# FTS_V1_0.net
KiCad netlist of a schematic drawn in EAGLE
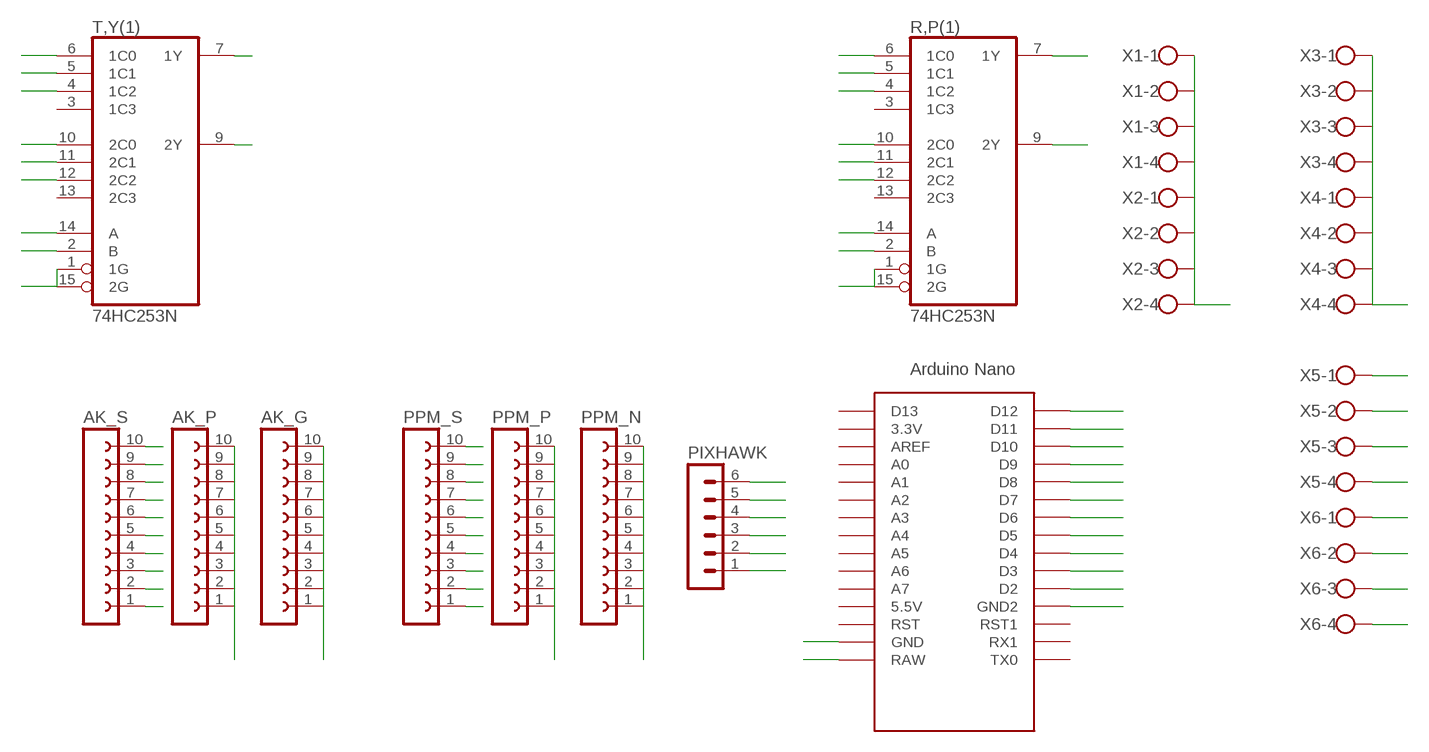
[diagram p0: schematic, sheet 1]

(export (version "E")
  (design (tool "Eeschema 10.0.6"))
  (components
    (comp (ref "AK_G")
      (value "FE10-1")
      (footprint "eagle-import:FE10")
      (libsource (lib "eagle-import") (part "FE10-1"))
    )
    (comp (ref "AK_P")
      (value "FE10-1")
      (footprint "eagle-import:FE10")
      (libsource (lib "eagle-import") (part "FE10-1"))
    )
    (comp (ref "AK_S")
      (value "FE10-1")
      (footprint "eagle-import:FE10")
      (libsource (lib "eagle-import") (part "FE10-1"))
    )
    (comp (ref "PIXHAWK")
      (value "MA06-1")
      (footprint "eagle-import:MA06-1")
      (libsource (lib "eagle-import") (part "MA06-1"))
    )
    (comp (ref "PPM_N")
      (value "FE10-1")
      (footprint "eagle-import:FE10")
      (libsource (lib "eagle-import") (part "FE10-1"))
    )
    (comp (ref "PPM_P")
      (value "FE10-1")
      (footprint "eagle-import:FE10")
      (libsource (lib "eagle-import") (part "FE10-1"))
    )
    (comp (ref "PPM_S")
      (value "FE10-1")
      (footprint "eagle-import:FE10")
      (libsource (lib "eagle-import") (part "FE10-1"))
    )
    (comp (ref "R,P(1)")
      (value "74HC253N")
      (footprint "eagle-import:DIL16")
      (libsource (lib "eagle-import") (part "74253NHC"))
    )
    (comp (ref "T,Y(1)")
      (value "74HC253N")
      (footprint "eagle-import:DIL16")
      (libsource (lib "eagle-import") (part "74253NHC"))
    )
    (comp (ref "U$1")
      (value "NANO")
      (footprint "eagle-import:NANO")
      (libsource (lib "eagle-import") (part "NANO"))
    )
    (comp (ref "X1")
      (value "W237-4")
      (footprint "eagle-import:W237-4")
      (libsource (lib "eagle-import") (part "W237-4"))
    )
    (comp (ref "X2")
      (value "W237-4")
      (footprint "eagle-import:W237-4")
      (libsource (lib "eagle-import") (part "W237-4"))
    )
    (comp (ref "X3")
      (value "W237-4")
      (footprint "eagle-import:W237-4")
      (libsource (lib "eagle-import") (part "W237-4"))
    )
    (comp (ref "X4")
      (value "W237-4")
      (footprint "eagle-import:W237-4")
      (libsource (lib "eagle-import") (part "W237-4"))
    )
    (comp (ref "X5")
      (value "W237-4")
      (footprint "eagle-import:W237-4")
      (libsource (lib "eagle-import") (part "W237-4"))
    )
    (comp (ref "X6")
      (value "W237-4")
      (footprint "eagle-import:W237-4")
      (libsource (lib "eagle-import") (part "W237-4"))
    )
  )
  (nets
    (net (code "1") (name "/AUX2") (class "Default")
      (node (ref "AK_S") (pin "7") (pinfunction "7_7") (pintype "passive"))
      (node (ref "U$1") (pin "D6") (pinfunction "D6_D6") (pintype "bidirectional"))
    )
    (net (code "2") (name "/DROP") (class "Default")
      (node (ref "AK_S") (pin "10") (pinfunction "10_10") (pintype "passive"))
      (node (ref "X6") (pin "4") (pinfunction "KL_4") (pintype "passive"))
    )
    (net (code "3") (name "/GBL-P") (class "Default")
      (node (ref "AK_S") (pin "9") (pinfunction "9_9") (pintype "passive"))
      (node (ref "X6") (pin "3") (pinfunction "KL_3") (pintype "passive"))
    )
    (net (code "4") (name "/GBL-R") (class "Default")
      (node (ref "AK_S") (pin "8") (pinfunction "8_8") (pintype "passive"))
      (node (ref "X6") (pin "2") (pinfunction "KL_2") (pintype "passive"))
    )
    (net (code "5") (name "/GEAR") (class "Default")
      (node (ref "AK_S") (pin "6") (pinfunction "6_6") (pintype "passive"))
      (node (ref "U$1") (pin "D5") (pinfunction "D5_D5") (pintype "bidirectional"))
    )
    (net (code "6") (name "/GND") (class "Default")
      (node (ref "AK_G") (pin "1") (pinfunction "1_1") (pintype "passive"))
      (node (ref "AK_G") (pin "10") (pinfunction "10_10") (pintype "passive"))
      (node (ref "AK_G") (pin "2") (pinfunction "2_2") (pintype "passive"))
      (node (ref "AK_G") (pin "3") (pinfunction "3_3") (pintype "passive"))
      (node (ref "AK_G") (pin "4") (pinfunction "4_4") (pintype "passive"))
      (node (ref "AK_G") (pin "5") (pinfunction "5_5") (pintype "passive"))
      (node (ref "AK_G") (pin "6") (pinfunction "6_6") (pintype "passive"))
      (node (ref "AK_G") (pin "7") (pinfunction "7_7") (pintype "passive"))
      (node (ref "AK_G") (pin "8") (pinfunction "8_8") (pintype "passive"))
      (node (ref "AK_G") (pin "9") (pinfunction "9_9") (pintype "passive"))
      (node (ref "PIXHAWK") (pin "6") (pinfunction "6_6") (pintype "passive"))
      (node (ref "PPM_N") (pin "1") (pinfunction "1_1") (pintype "passive"))
      (node (ref "PPM_N") (pin "10") (pinfunction "10_10") (pintype "passive"))
      (node (ref "PPM_N") (pin "2") (pinfunction "2_2") (pintype "passive"))
      (node (ref "PPM_N") (pin "3") (pinfunction "3_3") (pintype "passive"))
      (node (ref "PPM_N") (pin "4") (pinfunction "4_4") (pintype "passive"))
      (node (ref "PPM_N") (pin "5") (pinfunction "5_5") (pintype "passive"))
      (node (ref "PPM_N") (pin "6") (pinfunction "6_6") (pintype "passive"))
      (node (ref "PPM_N") (pin "7") (pinfunction "7_7") (pintype "passive"))
      (node (ref "PPM_N") (pin "8") (pinfunction "8_8") (pintype "passive"))
      (node (ref "PPM_N") (pin "9") (pinfunction "9_9") (pintype "passive"))
      (node (ref "R,P(1)") (pin "1") (pinfunction "1G_1") (pintype "input"))
      (node (ref "R,P(1)") (pin "15") (pinfunction "2G_15") (pintype "input"))
      (node (ref "T,Y(1)") (pin "1") (pinfunction "1G_1") (pintype "input"))
      (node (ref "T,Y(1)") (pin "15") (pinfunction "2G_15") (pintype "input"))
      (node (ref "U$1") (pin "GND") (pinfunction "GND_GND") (pintype "bidirectional"))
      (node (ref "U$1") (pin "GND1") (pinfunction "GND2_GND1") (pintype "bidirectional"))
      (node (ref "X3") (pin "1") (pinfunction "KL_1") (pintype "passive"))
      (node (ref "X3") (pin "2") (pinfunction "KL_2") (pintype "passive"))
      (node (ref "X3") (pin "3") (pinfunction "KL_3") (pintype "passive"))
      (node (ref "X3") (pin "4") (pinfunction "KL_4") (pintype "passive"))
      (node (ref "X4") (pin "1") (pinfunction "KL_1") (pintype "passive"))
      (node (ref "X4") (pin "2") (pinfunction "KL_2") (pintype "passive"))
      (node (ref "X4") (pin "3") (pinfunction "KL_3") (pintype "passive"))
      (node (ref "X4") (pin "4") (pinfunction "KL_4") (pintype "passive"))
    )
    (net (code "7") (name "/PX-P") (class "Default")
      (node (ref "PIXHAWK") (pin "2") (pinfunction "2_2") (pintype "passive"))
      (node (ref "R,P(1)") (pin "11") (pinfunction "2C1_11") (pintype "input"))
    )
    (net (code "8") (name "/PX-R") (class "Default")
      (node (ref "PIXHAWK") (pin "1") (pinfunction "1_1") (pintype "passive"))
      (node (ref "R,P(1)") (pin "5") (pinfunction "1C1_5") (pintype "input"))
    )
    (net (code "9") (name "/PX-T") (class "Default")
      (node (ref "PIXHAWK") (pin "3") (pinfunction "3_3") (pintype "passive"))
      (node (ref "T,Y(1)") (pin "5") (pinfunction "1C1_5") (pintype "input"))
    )
    (net (code "10") (name "/PX-Y") (class "Default")
      (node (ref "PIXHAWK") (pin "4") (pinfunction "4_4") (pintype "passive"))
      (node (ref "T,Y(1)") (pin "11") (pinfunction "2C1_11") (pintype "input"))
    )
    (net (code "11") (name "/RX-FM") (class "Default")
      (node (ref "AK_S") (pin "5") (pinfunction "5_5") (pintype "passive"))
      (node (ref "PPM_S") (pin "5") (pinfunction "5_5") (pintype "passive"))
    )
    (net (code "12") (name "/RX-P") (class "Default")
      (node (ref "AK_S") (pin "2") (pinfunction "2_2") (pintype "passive"))
      (node (ref "PPM_S") (pin "2") (pinfunction "2_2") (pintype "passive"))
      (node (ref "R,P(1)") (pin "10") (pinfunction "2C0_10") (pintype "input"))
    )
    (net (code "13") (name "/RX-R") (class "Default")
      (node (ref "AK_S") (pin "1") (pinfunction "1_1") (pintype "passive"))
      (node (ref "PPM_S") (pin "1") (pinfunction "1_1") (pintype "passive"))
      (node (ref "R,P(1)") (pin "6") (pinfunction "1C0_6") (pintype "input"))
    )
    (net (code "14") (name "/RX-T") (class "Default")
      (node (ref "AK_S") (pin "3") (pinfunction "3_3") (pintype "passive"))
      (node (ref "PPM_S") (pin "3") (pinfunction "3_3") (pintype "passive"))
      (node (ref "T,Y(1)") (pin "6") (pinfunction "1C0_6") (pintype "input"))
      (node (ref "U$1") (pin "D12") (pinfunction "D12_D12") (pintype "bidirectional"))
    )
    (net (code "15") (name "/RX-Y") (class "Default")
      (node (ref "AK_S") (pin "4") (pinfunction "4_4") (pintype "passive"))
      (node (ref "PPM_S") (pin "4") (pinfunction "4_4") (pintype "passive"))
      (node (ref "T,Y(1)") (pin "10") (pinfunction "2C0_10") (pintype "input"))
    )
    (net (code "16") (name "/S-P") (class "Default")
      (node (ref "R,P(1)") (pin "9") (pinfunction "2Y_9") (pintype "tri_state"))
      (node (ref "X5") (pin "2") (pinfunction "KL_2") (pintype "passive"))
    )
    (net (code "17") (name "/S-R") (class "Default")
      (node (ref "R,P(1)") (pin "7") (pinfunction "1Y_7") (pintype "tri_state"))
      (node (ref "X5") (pin "1") (pinfunction "KL_1") (pintype "passive"))
    )
    (net (code "18") (name "/S-T") (class "Default")
      (node (ref "T,Y(1)") (pin "7") (pinfunction "1Y_7") (pintype "tri_state"))
      (node (ref "X5") (pin "3") (pinfunction "KL_3") (pintype "passive"))
    )
    (net (code "19") (name "/S-Y") (class "Default")
      (node (ref "T,Y(1)") (pin "9") (pinfunction "2Y_9") (pintype "tri_state"))
      (node (ref "X5") (pin "4") (pinfunction "KL_4") (pintype "passive"))
      (node (ref "X6") (pin "1") (pinfunction "KL_1") (pintype "passive"))
    )
    (net (code "20") (name "/S1") (class "Default")
      (node (ref "R,P(1)") (pin "14") (pinfunction "A_14") (pintype "input"))
      (node (ref "T,Y(1)") (pin "14") (pinfunction "A_14") (pintype "input"))
      (node (ref "U$1") (pin "D2") (pinfunction "D2_D2") (pintype "bidirectional"))
    )
    (net (code "21") (name "/S2") (class "Default")
      (node (ref "R,P(1)") (pin "2") (pinfunction "B_2") (pintype "input"))
      (node (ref "T,Y(1)") (pin "2") (pinfunction "B_2") (pintype "input"))
      (node (ref "U$1") (pin "D3") (pinfunction "D3_D3") (pintype "bidirectional"))
    )
    (net (code "22") (name "/VCC") (class "Default")
      (node (ref "AK_P") (pin "1") (pinfunction "1_1") (pintype "passive"))
      (node (ref "AK_P") (pin "10") (pinfunction "10_10") (pintype "passive"))
      (node (ref "AK_P") (pin "2") (pinfunction "2_2") (pintype "passive"))
      (node (ref "AK_P") (pin "3") (pinfunction "3_3") (pintype "passive"))
      (node (ref "AK_P") (pin "4") (pinfunction "4_4") (pintype "passive"))
      (node (ref "AK_P") (pin "5") (pinfunction "5_5") (pintype "passive"))
      (node (ref "AK_P") (pin "6") (pinfunction "6_6") (pintype "passive"))
      (node (ref "AK_P") (pin "7") (pinfunction "7_7") (pintype "passive"))
      (node (ref "AK_P") (pin "8") (pinfunction "8_8") (pintype "passive"))
      (node (ref "AK_P") (pin "9") (pinfunction "9_9") (pintype "passive"))
      (node (ref "PPM_P") (pin "1") (pinfunction "1_1") (pintype "passive"))
      (node (ref "PPM_P") (pin "10") (pinfunction "10_10") (pintype "passive"))
      (node (ref "PPM_P") (pin "2") (pinfunction "2_2") (pintype "passive"))
      (node (ref "PPM_P") (pin "3") (pinfunction "3_3") (pintype "passive"))
      (node (ref "PPM_P") (pin "4") (pinfunction "4_4") (pintype "passive"))
      (node (ref "PPM_P") (pin "5") (pinfunction "5_5") (pintype "passive"))
      (node (ref "PPM_P") (pin "6") (pinfunction "6_6") (pintype "passive"))
      (node (ref "PPM_P") (pin "7") (pinfunction "7_7") (pintype "passive"))
      (node (ref "PPM_P") (pin "8") (pinfunction "8_8") (pintype "passive"))
      (node (ref "PPM_P") (pin "9") (pinfunction "9_9") (pintype "passive"))
      (node (ref "U$1") (pin "RAW") (pinfunction "RAW_RAW") (pintype "bidirectional"))
      (node (ref "X1") (pin "1") (pinfunction "KL_1") (pintype "passive"))
      (node (ref "X1") (pin "2") (pinfunction "KL_2") (pintype "passive"))
      (node (ref "X1") (pin "3") (pinfunction "KL_3") (pintype "passive"))
      (node (ref "X1") (pin "4") (pinfunction "KL_4") (pintype "passive"))
      (node (ref "X2") (pin "1") (pinfunction "KL_1") (pintype "passive"))
      (node (ref "X2") (pin "2") (pinfunction "KL_2") (pintype "passive"))
      (node (ref "X2") (pin "3") (pinfunction "KL_3") (pintype "passive"))
      (node (ref "X2") (pin "4") (pinfunction "KL_4") (pintype "passive"))
    )
    (net (code "23") (name "unconnected-(PIXHAWK-Pad5)") (class "Default")
      (node (ref "PIXHAWK") (pin "5") (pinfunction "5_5") (pintype "passive"))
    )
    (net (code "24") (name "unconnected-(PPM_S-Pad6)") (class "Default")
      (node (ref "PPM_S") (pin "6") (pinfunction "6_6") (pintype "passive"))
    )
    (net (code "25") (name "unconnected-(PPM_S-Pad7)") (class "Default")
      (node (ref "PPM_S") (pin "7") (pinfunction "7_7") (pintype "passive"))
    )
    (net (code "26") (name "unconnected-(PPM_S-Pad8)") (class "Default")
      (node (ref "PPM_S") (pin "8") (pinfunction "8_8") (pintype "passive"))
    )
    (net (code "27") (name "unconnected-(PPM_S-Pad9)") (class "Default")
      (node (ref "PPM_S") (pin "9") (pinfunction "9_9") (pintype "passive"))
    )
    (net (code "28") (name "unconnected-(PPM_S-Pad10)") (class "Default")
      (node (ref "PPM_S") (pin "10") (pinfunction "10_10") (pintype "passive"))
    )
    (net (code "29") (name "unconnected-(R,P(1)A-1C2-Pad4)") (class "Default")
      (node (ref "R,P(1)") (pin "4") (pinfunction "1C2_4") (pintype "input"))
    )
    (net (code "30") (name "unconnected-(R,P(1)A-1C3-Pad3)") (class "Default")
      (node (ref "R,P(1)") (pin "3") (pinfunction "1C3_3") (pintype "input"))
    )
    (net (code "31") (name "unconnected-(R,P(1)A-2C2-Pad12)") (class "Default")
      (node (ref "R,P(1)") (pin "12") (pinfunction "2C2_12") (pintype "input"))
    )
    (net (code "32") (name "unconnected-(R,P(1)A-2C3-Pad13)") (class "Default")
      (node (ref "R,P(1)") (pin "13") (pinfunction "2C3_13") (pintype "input"))
    )
    (net (code "33") (name "unconnected-(T,Y(1)A-1C2-Pad4)") (class "Default")
      (node (ref "T,Y(1)") (pin "4") (pinfunction "1C2_4") (pintype "input"))
    )
    (net (code "34") (name "unconnected-(T,Y(1)A-1C3-Pad3)") (class "Default")
      (node (ref "T,Y(1)") (pin "3") (pinfunction "1C3_3") (pintype "input"))
    )
    (net (code "35") (name "unconnected-(T,Y(1)A-2C2-Pad12)") (class "Default")
      (node (ref "T,Y(1)") (pin "12") (pinfunction "2C2_12") (pintype "input"))
    )
    (net (code "36") (name "unconnected-(T,Y(1)A-2C3-Pad13)") (class "Default")
      (node (ref "T,Y(1)") (pin "13") (pinfunction "2C3_13") (pintype "input"))
    )
    (net (code "37") (name "unconnected-(U$1-5.5V-Pad5V)") (class "Default")
      (node (ref "U$1") (pin "5V") (pinfunction "5.5V_5V") (pintype "bidirectional"))
    )
    (net (code "38") (name "unconnected-(U$1-Pad3.3V)") (class "Default")
      (node (ref "U$1") (pin "3.3V") (pinfunction "3.3V_3.3V") (pintype "bidirectional"))
    )
    (net (code "39") (name "unconnected-(U$1-PadA0)") (class "Default")
      (node (ref "U$1") (pin "A0") (pinfunction "A0_A0") (pintype "bidirectional"))
    )
    (net (code "40") (name "unconnected-(U$1-PadA1)") (class "Default")
      (node (ref "U$1") (pin "A1") (pinfunction "A1_A1") (pintype "bidirectional"))
    )
    (net (code "41") (name "unconnected-(U$1-PadA2)") (class "Default")
      (node (ref "U$1") (pin "A2") (pinfunction "A2_A2") (pintype "bidirectional"))
    )
    (net (code "42") (name "unconnected-(U$1-PadA3)") (class "Default")
      (node (ref "U$1") (pin "A3") (pinfunction "A3_A3") (pintype "bidirectional"))
    )
    (net (code "43") (name "unconnected-(U$1-PadA4)") (class "Default")
      (node (ref "U$1") (pin "A4") (pinfunction "A4_A4") (pintype "bidirectional"))
    )
    (net (code "44") (name "unconnected-(U$1-PadA5)") (class "Default")
      (node (ref "U$1") (pin "A5") (pinfunction "A5_A5") (pintype "bidirectional"))
    )
    (net (code "45") (name "unconnected-(U$1-PadA6)") (class "Default")
      (node (ref "U$1") (pin "A6") (pinfunction "A6_A6") (pintype "bidirectional"))
    )
    (net (code "46") (name "unconnected-(U$1-PadA7)") (class "Default")
      (node (ref "U$1") (pin "A7") (pinfunction "A7_A7") (pintype "bidirectional"))
    )
    (net (code "47") (name "unconnected-(U$1-PadAREF)") (class "Default")
      (node (ref "U$1") (pin "AREF") (pinfunction "AREF_AREF") (pintype "bidirectional"))
    )
    (net (code "48") (name "unconnected-(U$1-PadD4)") (class "Default")
      (node (ref "U$1") (pin "D4") (pinfunction "D4_D4") (pintype "bidirectional"))
    )
    (net (code "49") (name "unconnected-(U$1-PadD7)") (class "Default")
      (node (ref "U$1") (pin "D7") (pinfunction "D7_D7") (pintype "bidirectional"))
    )
    (net (code "50") (name "unconnected-(U$1-PadD8)") (class "Default")
      (node (ref "U$1") (pin "D8") (pinfunction "D8_D8") (pintype "bidirectional"))
    )
    (net (code "51") (name "unconnected-(U$1-PadD9)") (class "Default")
      (node (ref "U$1") (pin "D9") (pinfunction "D9_D9") (pintype "bidirectional"))
    )
    (net (code "52") (name "unconnected-(U$1-PadD10)") (class "Default")
      (node (ref "U$1") (pin "D10") (pinfunction "D10_D10") (pintype "bidirectional"))
    )
    (net (code "53") (name "unconnected-(U$1-PadD11)") (class "Default")
      (node (ref "U$1") (pin "D11") (pinfunction "D11_D11") (pintype "bidirectional"))
    )
    (net (code "54") (name "unconnected-(U$1-PadD13)") (class "Default")
      (node (ref "U$1") (pin "D13") (pinfunction "D13_D13") (pintype "bidirectional"))
    )
    (net (code "55") (name "unconnected-(U$1-PadICSP1)") (class "Default")
      (node (ref "U$1") (pin "ICSP1") (pinfunction "ICSP1_ICSP1") (pintype "bidirectional"))
    )
    (net (code "56") (name "unconnected-(U$1-PadICSP2)") (class "Default")
      (node (ref "U$1") (pin "ICSP2") (pinfunction "ICSP2_ICSP2") (pintype "bidirectional"))
    )
    (net (code "57") (name "unconnected-(U$1-PadICSP3)") (class "Default")
      (node (ref "U$1") (pin "ICSP3") (pinfunction "ICSP3_ICSP3") (pintype "bidirectional"))
    )
    (net (code "58") (name "unconnected-(U$1-PadICSP4)") (class "Default")
      (node (ref "U$1") (pin "ICSP4") (pinfunction "ICSP4_ICSP4") (pintype "bidirectional"))
    )
    (net (code "59") (name "unconnected-(U$1-PadICSP5)") (class "Default")
      (node (ref "U$1") (pin "ICSP5") (pinfunction "ICSP5_ICSP5") (pintype "bidirectional"))
    )
    (net (code "60") (name "unconnected-(U$1-PadICSP6)") (class "Default")
      (node (ref "U$1") (pin "ICSP6") (pinfunction "ICSP6_ICSP6") (pintype "bidirectional"))
    )
    (net (code "61") (name "unconnected-(U$1-PadRST)") (class "Default")
      (node (ref "U$1") (pin "RST") (pinfunction "RST_RST") (pintype "bidirectional"))
    )
    (net (code "62") (name "unconnected-(U$1-PadRST1)") (class "Default")
      (node (ref "U$1") (pin "RST1") (pinfunction "RST1_RST1") (pintype "bidirectional"))
    )
    (net (code "63") (name "unconnected-(U$1-PadRX1)") (class "Default")
      (node (ref "U$1") (pin "RX1") (pinfunction "RX1_RX1") (pintype "bidirectional"))
    )
    (net (code "64") (name "unconnected-(U$1-PadTX0)") (class "Default")
      (node (ref "U$1") (pin "TX0") (pinfunction "TX0_TX0") (pintype "bidirectional"))
    )
  )
)
